# lm3410-sepic-flashlight-driver-17mm-mk-1.net
KiCad netlist of a schematic drawn in EAGLE
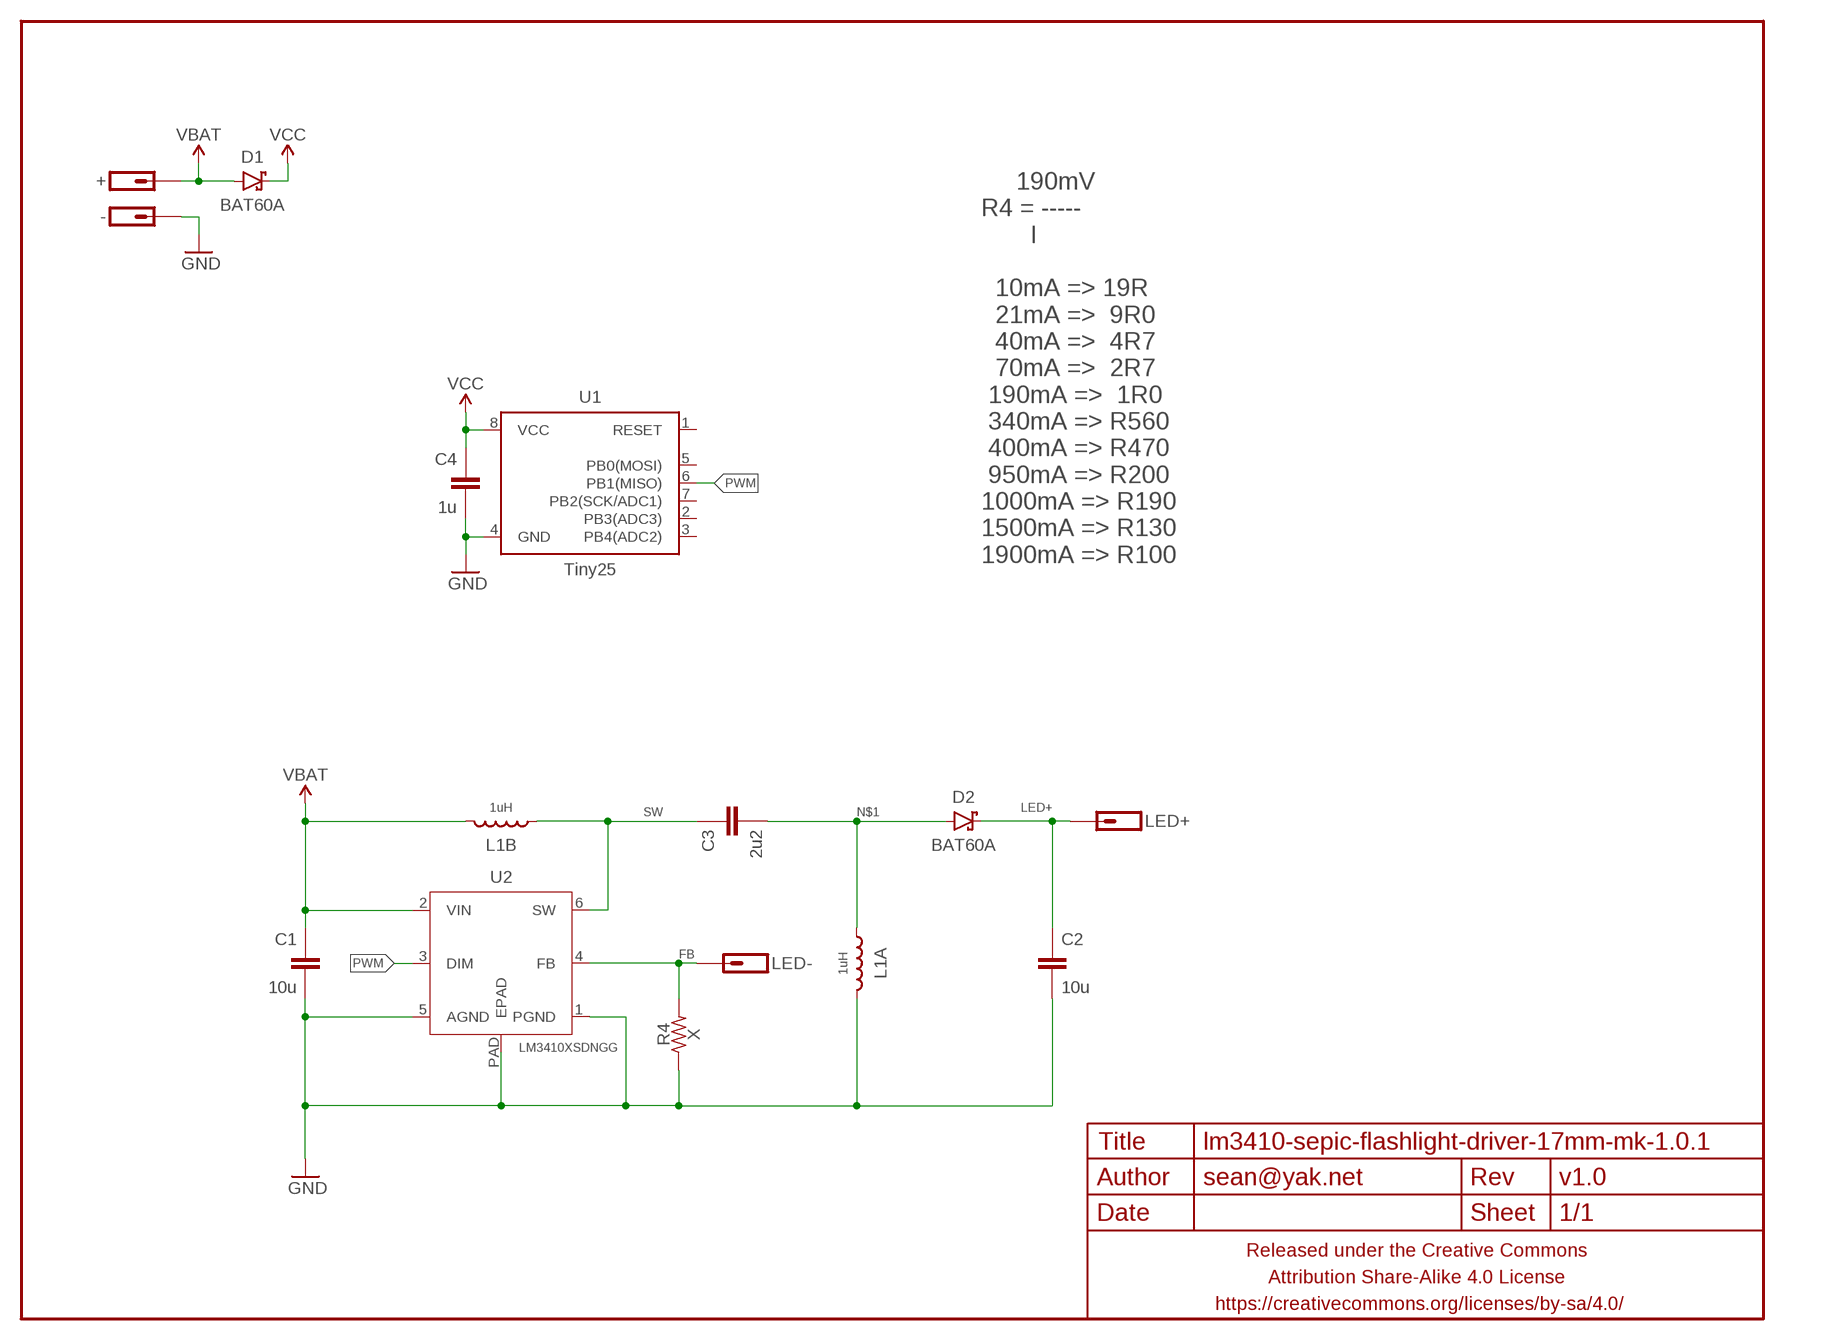
[diagram p0: schematic, sheet 1]

(export (version "E")
  (design (tool "Eeschema 10.0.6"))
  (components
    (comp (ref "+")
      (value "M01NOT-A-VIA-NOPE")
      (footprint "eagle-import:1X01_NOSILK_NOSTOP")
      (libsource (lib "eagle-import") (part "M01NOT-A-VIA-NOPE"))
    )
    (comp (ref "-")
      (value "M01NOT-A-VIA-NOPE")
      (footprint "eagle-import:1X01_NOSILK_NOSTOP")
      (libsource (lib "eagle-import") (part "M01NOT-A-VIA-NOPE"))
    )
    (comp (ref "C1")
      (value "10u")
      (footprint "eagle-import:C0603-TIGHTER")
      (libsource (lib "eagle-import") (part "CAPACITOR-CERAMICC0603-TIGHTER"))
    )
    (comp (ref "C2")
      (value "10u")
      (footprint "eagle-import:C0603-TIGHTER")
      (libsource (lib "eagle-import") (part "CAPACITOR-CERAMICC0603-TIGHTER"))
    )
    (comp (ref "C3")
      (value "2u2")
      (footprint "eagle-import:C0603-TIGHTER")
      (libsource (lib "eagle-import") (part "CAPACITOR-CERAMICC0603-TIGHTER"))
    )
    (comp (ref "C4")
      (value "1u")
      (footprint "eagle-import:C0603-TIGHTER")
      (libsource (lib "eagle-import") (part "CAPACITOR-CERAMICC0603-TIGHTER"))
    )
    (comp (ref "D1")
      (value "BAT60A")
      (footprint "eagle-import:SOD323-SCHOTTKY")
      (libsource (lib "eagle-import") (part "DIODE-SCHOTTKYSOD323"))
    )
    (comp (ref "D2")
      (value "BAT60A")
      (footprint "eagle-import:SOD323-SCHOTTKY")
      (libsource (lib "eagle-import") (part "DIODE-SCHOTTKYSOD323"))
    )
    (comp (ref "FRAME1")
      (value "FRAME-LETTERNO_PACKAGE")
      (footprint "eagle-import:DUMMY")
      (fields (field (name "DESIGNER") "sean@yak.net") (field (name "VERSION") "v1.0"))
      (libsource (lib "eagle-import") (part "FRAME-LETTERNO_PACKAGE"))
    )
    (comp (ref "L1")
      (value "1uH")
      (footprint "eagle-import:LPD5030")
      (libsource (lib "eagle-import") (part "INDUCTOR-DUALCOILCRAFT-LPD5030"))
    )
    (comp (ref "LED+")
      (value "M01PTH-1MM-CIR-NS")
      (footprint "eagle-import:1X01-1MM-CIR-NS")
      (libsource (lib "eagle-import") (part "M01PTH-1MM-CIR-NS"))
    )
    (comp (ref "LED-")
      (value "M01PTH-1MM-CIR-NS")
      (footprint "eagle-import:1X01-1MM-CIR-NS")
      (libsource (lib "eagle-import") (part "M01PTH-1MM-CIR-NS"))
    )
    (comp (ref "R4")
      (value "X")
      (footprint "eagle-import:R0805-TIGHTER")
      (libsource (lib "eagle-import") (part "RESISTORR0805-TIGHTER"))
    )
    (comp (ref "U1")
      (value "Tiny25")
      (footprint "eagle-import:SO08-SKINNYPADS")
      (libsource (lib "eagle-import") (part "ATTINY45TINY25-SOICN-NARROWER"))
    )
    (comp (ref "U2")
      (value "LM3410XSDNGG")
      (footprint "eagle-import:DFN300X300X80-7N")
      (fields (field (name "MPN") "LM3410XSD"))
      (libsource (lib "eagle-import") (part "LM3410XSDNGG"))
    )
  )
  (nets
    (net (code "1") (name "/FB") (class "Default")
      (node (ref "LED-") (pin "1") (pinfunction "1_1") (pintype "passive"))
      (node (ref "R4") (pin "2") (pinfunction "2_2") (pintype "passive"))
      (node (ref "U2") (pin "4") (pinfunction "FB_4") (pintype "input"))
    )
    (net (code "2") (name "/LED+") (class "Default")
      (node (ref "C2") (pin "1") (pinfunction "1_1") (pintype "passive"))
      (node (ref "D2") (pin "C") (pinfunction "C_C") (pintype "passive"))
      (node (ref "LED+") (pin "1") (pinfunction "1_1") (pintype "passive"))
    )
    (net (code "3") (name "/N$1") (class "Default")
      (node (ref "C3") (pin "2") (pinfunction "2_2") (pintype "passive"))
      (node (ref "D2") (pin "A") (pinfunction "A_A") (pintype "passive"))
      (node (ref "L1") (pin "1") (pinfunction "1_1") (pintype "passive"))
    )
    (net (code "4") (name "/SW") (class "Default")
      (node (ref "C3") (pin "1") (pinfunction "1_1") (pintype "passive"))
      (node (ref "L1") (pin "4") (pinfunction "1_4") (pintype "passive"))
      (node (ref "U2") (pin "6") (pinfunction "SW_6") (pintype "output"))
    )
    (net (code "5") (name "GND") (class "Default")
      (node (ref "-") (pin "P$1") (pinfunction "1_P$1") (pintype "passive"))
      (node (ref "C1") (pin "2") (pinfunction "2_2") (pintype "passive"))
      (node (ref "C2") (pin "2") (pinfunction "2_2") (pintype "passive"))
      (node (ref "C4") (pin "2") (pinfunction "2_2") (pintype "passive"))
      (node (ref "L1") (pin "2") (pinfunction "2_2") (pintype "passive"))
      (node (ref "R4") (pin "1") (pinfunction "1_1") (pintype "passive"))
      (node (ref "U1") (pin "4") (pinfunction "GND_4") (pintype "bidirectional"))
      (node (ref "U2") (pin "1") (pinfunction "PGND_1") (pintype "passive"))
      (node (ref "U2") (pin "5") (pinfunction "AGND_5") (pintype "passive"))
      (node (ref "U2") (pin "PAD") (pinfunction "EPAD_PAD") (pintype "passive"))
    )
    (net (code "6") (name "PWM") (class "Default")
      (node (ref "U1") (pin "6") (pinfunction "PB1(MISO)_6") (pintype "bidirectional"))
      (node (ref "U2") (pin "3") (pinfunction "DIM_3") (pintype "input"))
    )
    (net (code "7") (name "VBAT") (class "Default")
      (node (ref "+") (pin "P$1") (pinfunction "1_P$1") (pintype "passive"))
      (node (ref "C1") (pin "1") (pinfunction "1_1") (pintype "passive"))
      (node (ref "D1") (pin "A") (pinfunction "A_A") (pintype "passive"))
      (node (ref "L1") (pin "3") (pinfunction "2_3") (pintype "passive"))
      (node (ref "U2") (pin "2") (pinfunction "VIN_2") (pintype "power_in"))
    )
    (net (code "8") (name "VCC") (class "Default")
      (node (ref "C4") (pin "1") (pinfunction "1_1") (pintype "passive"))
      (node (ref "D1") (pin "C") (pinfunction "C_C") (pintype "passive"))
      (node (ref "U1") (pin "8") (pinfunction "VCC_8") (pintype "bidirectional"))
    )
    (net (code "9") (name "unconnected-(U1-PB0(MOSI)-Pad5)") (class "Default")
      (node (ref "U1") (pin "5") (pinfunction "PB0(MOSI)_5") (pintype "bidirectional"))
    )
    (net (code "10") (name "unconnected-(U1-PB2(SCK{slash}ADC1)-Pad7)") (class "Default")
      (node (ref "U1") (pin "7") (pinfunction "PB2(SCK/ADC1)_7") (pintype "bidirectional"))
    )
    (net (code "11") (name "unconnected-(U1-PB3(ADC3)-Pad2)") (class "Default")
      (node (ref "U1") (pin "2") (pinfunction "PB3(ADC3)_2") (pintype "bidirectional"))
    )
    (net (code "12") (name "unconnected-(U1-PB4(ADC2)-Pad3)") (class "Default")
      (node (ref "U1") (pin "3") (pinfunction "PB4(ADC2)_3") (pintype "bidirectional"))
    )
    (net (code "13") (name "unconnected-(U1-RESET-Pad1)") (class "Default")
      (node (ref "U1") (pin "1") (pinfunction "RESET_1") (pintype "bidirectional"))
    )
  )
)
